# SCH_DHT_projetos_2022-03-18.net
KiCad netlist of a schematic drawn in EasyEDA
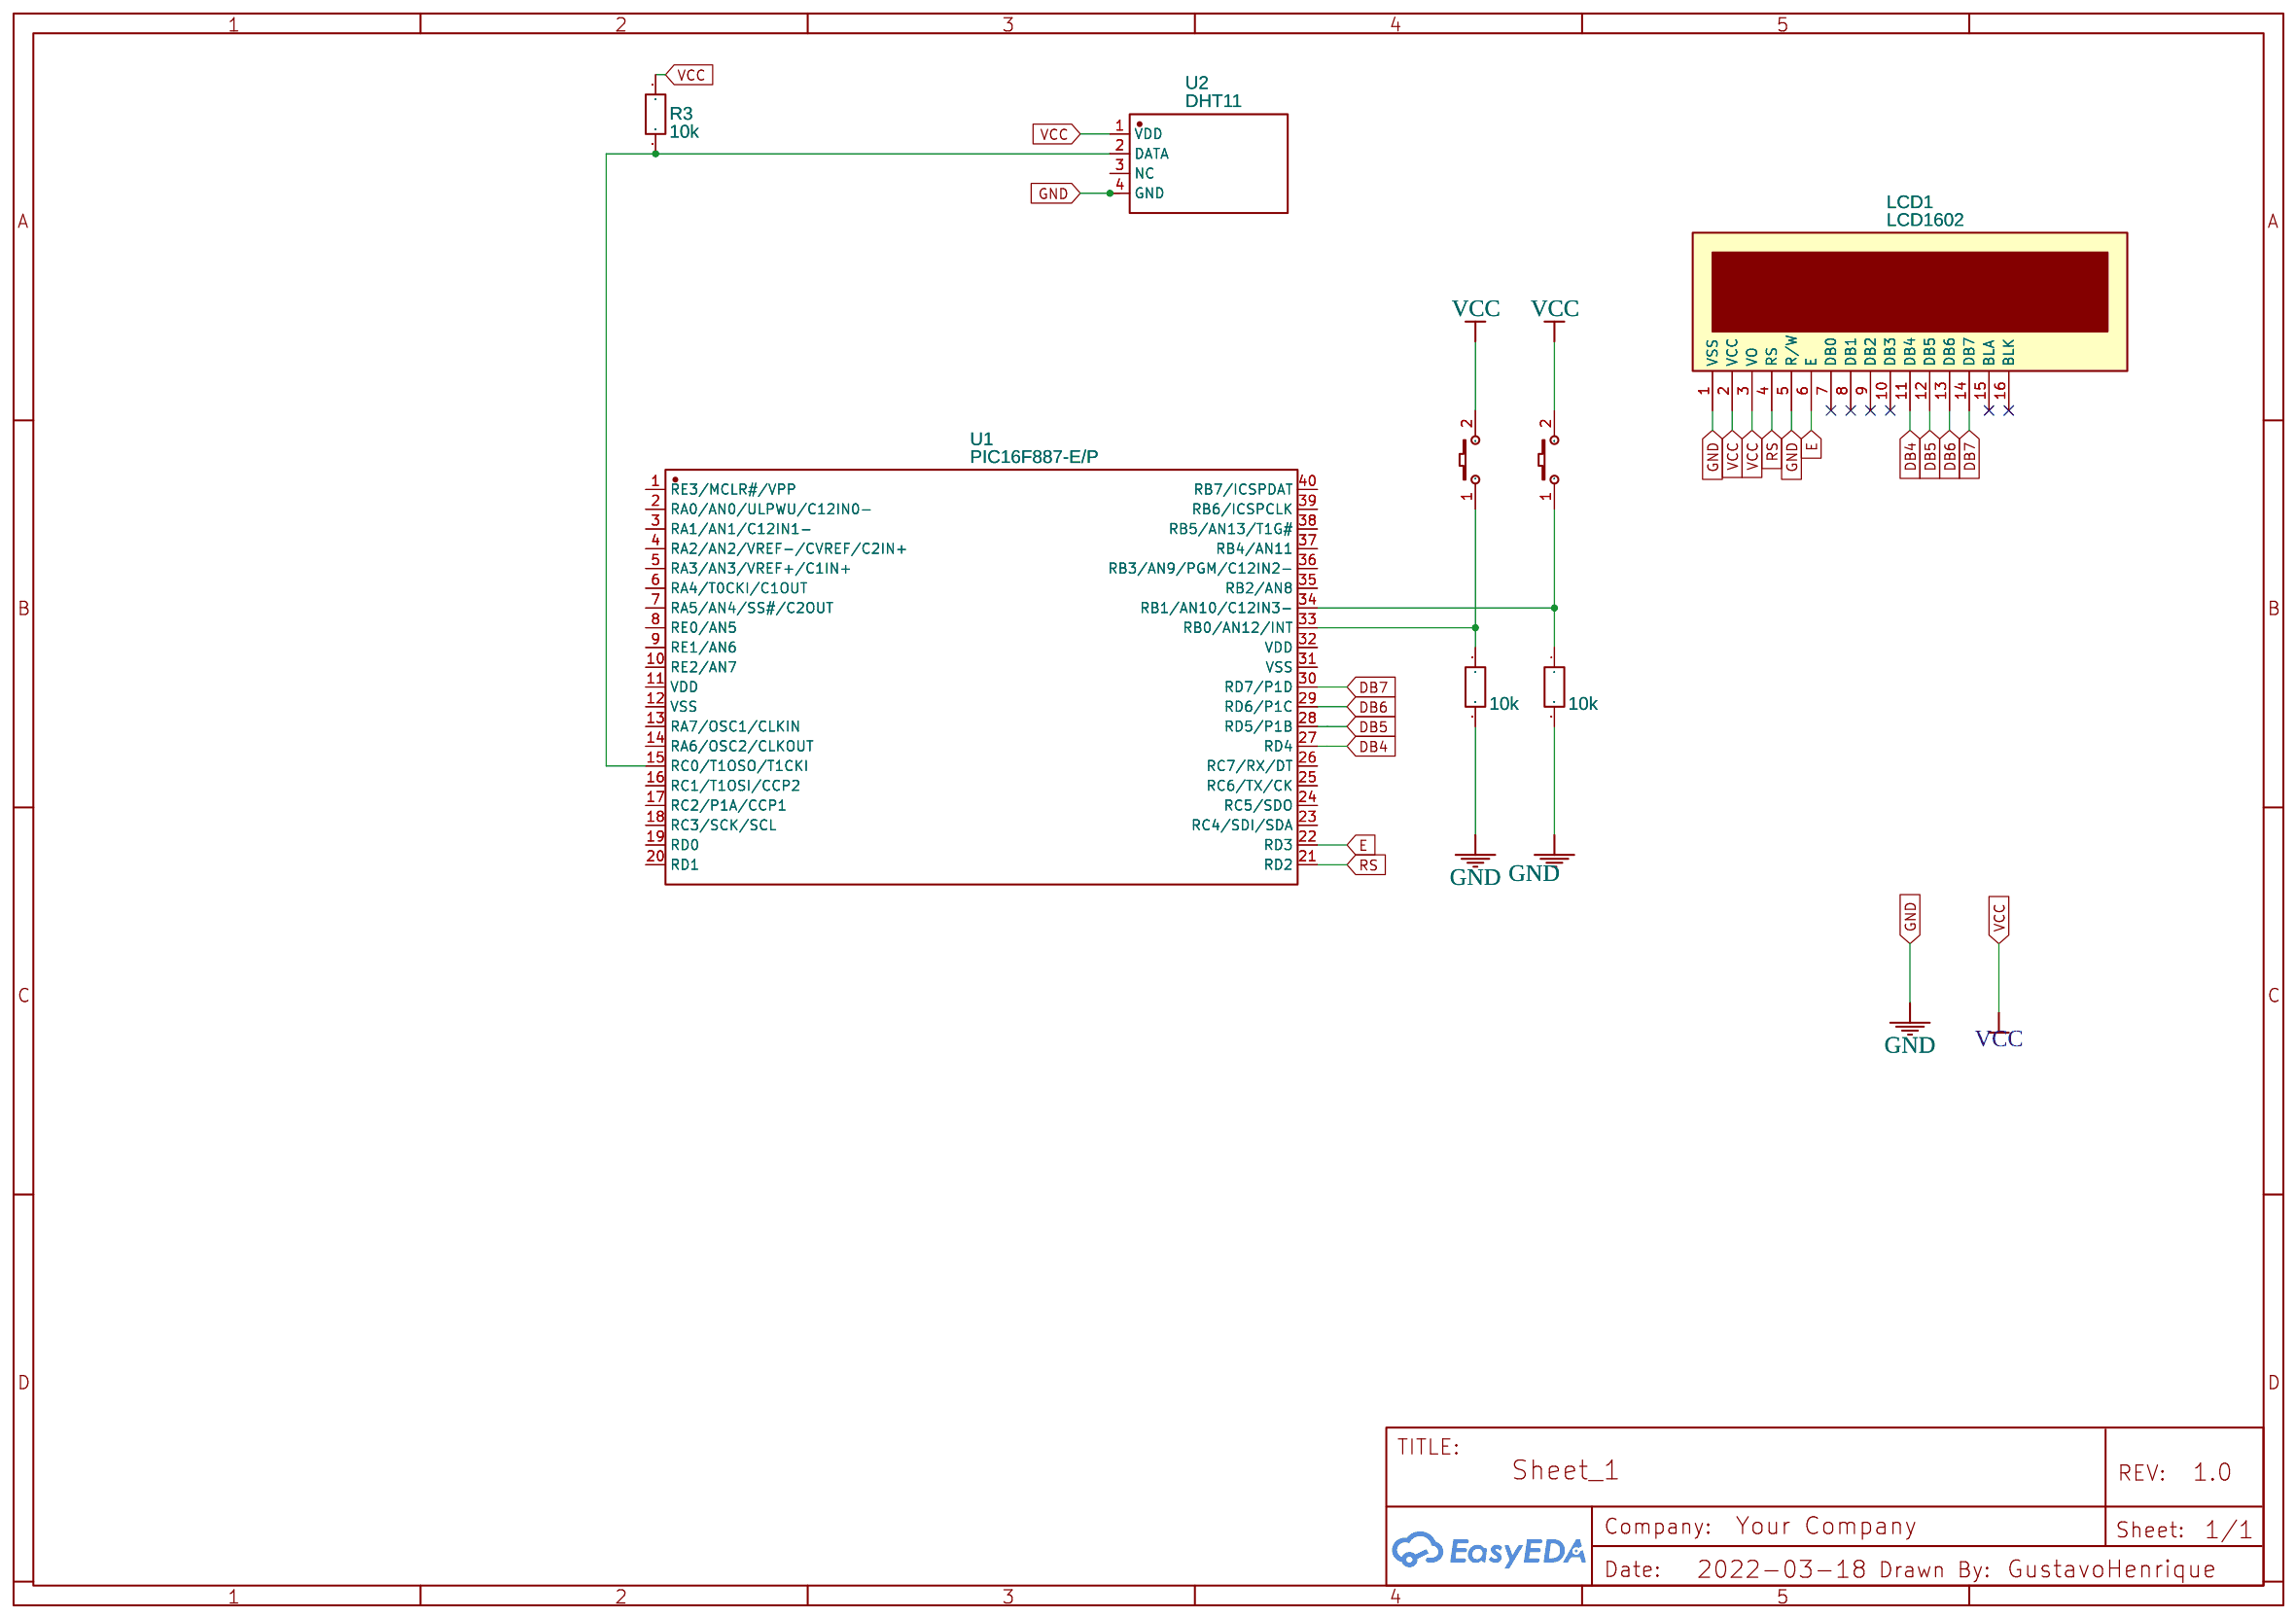
[diagram p0: schematic sheet]

(export (version "E")
  (design (tool "Eeschema 10.0.6"))
  (components
    (comp (ref "KEY1")
      (value "K2-3.6×6.1_SMD")
      (fields
        (field (name "BOM_Manufacturer Part") "K2-1107ST-A4SW-06")
        (field (name "BOM_Supplier Part") "C118141")
      )
      (libsource (lib "") (part "K2-3.6×6.1_SMD"))
    )
    (comp (ref "KEY2")
      (value "K2-3.6×6.1_SMD")
      (fields
        (field (name "BOM_Manufacturer Part") "K2-1107ST-A4SW-06")
        (field (name "BOM_Supplier Part") "C118141")
      )
      (libsource (lib "") (part "K2-3.6×6.1_SMD"))
    )
    (comp (ref "LCD1")
      (value "LCD1602")
      (fields
        (field (name "BOM_Manufacturer Part") "LCM1602K-NSW-BBW")
        (field (name "BOM_Supplier Part") "C83275")
      )
      (libsource (lib "") (part "LCD1602"))
    )
    (comp (ref "R1") (value "10k") (libsource (lib "") (part "R_0603_EU")))
    (comp (ref "R2") (value "10k") (libsource (lib "") (part "R_0603_EU")))
    (comp (ref "R3") (value "10k") (libsource (lib "") (part "R_0603_EU")))
    (comp (ref "U1")
      (value "PIC16F887-E/P")
      (fields (field (name "BOM_Supplier Part") "C647863"))
      (libsource (lib "") (part "PIC16F887-E/P"))
    )
    (comp (ref "U2")
      (value "DHT11")
      (fields (field (name "BOM_Supplier Part") "C117051"))
      (libsource (lib "") (part "DHT11"))
    )
  )
  (nets
    (net (code "1") (name "DB4") (class "Default")
      (node (ref "LCD1") (pin "11") (pinfunction "DB4_11") (pintype "unspecified"))
      (node (ref "U1") (pin "27") (pinfunction "RD4_27") (pintype "unspecified"))
    )
    (net (code "2") (name "DB5") (class "Default")
      (node (ref "LCD1") (pin "12") (pinfunction "DB5_12") (pintype "unspecified"))
      (node (ref "U1") (pin "28") (pinfunction "RD5/P1B_28") (pintype "unspecified"))
    )
    (net (code "3") (name "DB6") (class "Default")
      (node (ref "LCD1") (pin "13") (pinfunction "DB6_13") (pintype "unspecified"))
      (node (ref "U1") (pin "29") (pinfunction "RD6/P1C_29") (pintype "unspecified"))
    )
    (net (code "4") (name "DB7") (class "Default")
      (node (ref "LCD1") (pin "14") (pinfunction "DB7_14") (pintype "unspecified"))
      (node (ref "U1") (pin "30") (pinfunction "RD7/P1D_30") (pintype "unspecified"))
    )
    (net (code "5") (name "E") (class "Default")
      (node (ref "LCD1") (pin "6") (pinfunction "E_6") (pintype "unspecified"))
      (node (ref "U1") (pin "22") (pinfunction "RD3_22") (pintype "unspecified"))
    )
    (net (code "6") (name "GND") (class "Default")
      (node (ref "LCD1") (pin "1") (pinfunction "VSS_1") (pintype "unspecified"))
      (node (ref "LCD1") (pin "5") (pinfunction "R/W_5") (pintype "unspecified"))
      (node (ref "R1") (pin "2") (pinfunction "2_2") (pintype "unspecified"))
      (node (ref "R2") (pin "2") (pinfunction "2_2") (pintype "unspecified"))
      (node (ref "U2") (pin "4") (pinfunction "GND_4") (pintype "unspecified"))
    )
    (net (code "7") (name "Net-(U1-RB0{slash}AN12{slash}INT)") (class "Default")
      (node (ref "KEY1") (pin "1") (pinfunction "1_1") (pintype "unspecified"))
      (node (ref "R1") (pin "1") (pinfunction "1_1") (pintype "unspecified"))
      (node (ref "U1") (pin "33") (pinfunction "RB0/AN12/INT_33") (pintype "unspecified"))
    )
    (net (code "8") (name "Net-(U1-RB1{slash}AN10{slash}C12IN3-)") (class "Default")
      (node (ref "KEY2") (pin "1") (pinfunction "1_1") (pintype "unspecified"))
      (node (ref "R2") (pin "1") (pinfunction "1_1") (pintype "unspecified"))
      (node (ref "U1") (pin "34") (pinfunction "RB1/AN10/C12IN3-_34") (pintype "unspecified"))
    )
    (net (code "9") (name "Net-(U1-RC0{slash}T1OSO{slash}T1CKI)") (class "Default")
      (node (ref "R3") (pin "2") (pinfunction "2_2") (pintype "unspecified"))
      (node (ref "U1") (pin "15") (pinfunction "RC0/T1OSO/T1CKI_15") (pintype "unspecified"))
      (node (ref "U2") (pin "2") (pinfunction "DATA_2") (pintype "unspecified"))
    )
    (net (code "10") (name "RS") (class "Default")
      (node (ref "LCD1") (pin "4") (pinfunction "RS_4") (pintype "unspecified"))
      (node (ref "U1") (pin "21") (pinfunction "RD2_21") (pintype "unspecified"))
    )
    (net (code "11") (name "VCC") (class "Default")
      (node (ref "KEY1") (pin "2") (pinfunction "2_2") (pintype "unspecified"))
      (node (ref "KEY2") (pin "2") (pinfunction "2_2") (pintype "unspecified"))
      (node (ref "LCD1") (pin "2") (pinfunction "VCC_2") (pintype "unspecified"))
      (node (ref "LCD1") (pin "3") (pinfunction "VO_3") (pintype "unspecified"))
      (node (ref "R3") (pin "1") (pinfunction "1_1") (pintype "unspecified"))
      (node (ref "U2") (pin "1") (pinfunction "VDD_1") (pintype "unspecified"))
    )
    (net (code "12") (name "unconnected-(LCD1-BLA-Pad15)") (class "Default")
      (node (ref "LCD1") (pin "15") (pinfunction "BLA_15") (pintype "unspecified+no_connect"))
    )
    (net (code "13") (name "unconnected-(LCD1-BLK-Pad16)") (class "Default")
      (node (ref "LCD1") (pin "16") (pinfunction "BLK_16") (pintype "unspecified+no_connect"))
    )
    (net (code "14") (name "unconnected-(LCD1-DB0-Pad7)") (class "Default")
      (node (ref "LCD1") (pin "7") (pinfunction "DB0_7") (pintype "unspecified+no_connect"))
    )
    (net (code "15") (name "unconnected-(LCD1-DB1-Pad8)") (class "Default")
      (node (ref "LCD1") (pin "8") (pinfunction "DB1_8") (pintype "unspecified+no_connect"))
    )
    (net (code "16") (name "unconnected-(LCD1-DB2-Pad9)") (class "Default")
      (node (ref "LCD1") (pin "9") (pinfunction "DB2_9") (pintype "unspecified+no_connect"))
    )
    (net (code "17") (name "unconnected-(LCD1-DB3-Pad10)") (class "Default")
      (node (ref "LCD1") (pin "10") (pinfunction "DB3_10") (pintype "unspecified+no_connect"))
    )
    (net (code "18") (name "unconnected-(U1-RA0{slash}AN0{slash}ULPWU{slash}C12IN0--Pad2)") (class "Default")
      (node (ref "U1") (pin "2") (pinfunction "RA0/AN0/ULPWU/C12IN0-_2") (pintype "unspecified"))
    )
    (net (code "19") (name "unconnected-(U1-RA1{slash}AN1{slash}C12IN1--Pad3)") (class "Default")
      (node (ref "U1") (pin "3") (pinfunction "RA1/AN1/C12IN1-_3") (pintype "unspecified"))
    )
    (net (code "20") (name "unconnected-(U1-RA2{slash}AN2{slash}VREF-{slash}CVREF{slash}C2IN+-Pad4)") (class "Default")
      (node (ref "U1") (pin "4") (pinfunction "RA2/AN2/VREF-/CVREF/C2IN+_4") (pintype "unspecified"))
    )
    (net (code "21") (name "unconnected-(U1-RA3{slash}AN3{slash}VREF+{slash}C1IN+-Pad5)") (class "Default")
      (node (ref "U1") (pin "5") (pinfunction "RA3/AN3/VREF+/C1IN+_5") (pintype "unspecified"))
    )
    (net (code "22") (name "unconnected-(U1-RA4{slash}T0CKI{slash}C1OUT-Pad6)") (class "Default")
      (node (ref "U1") (pin "6") (pinfunction "RA4/T0CKI/C1OUT_6") (pintype "unspecified"))
    )
    (net (code "23") (name "unconnected-(U1-RA5{slash}AN4{slash}SS#{slash}C2OUT-Pad7)") (class "Default")
      (node (ref "U1") (pin "7") (pinfunction "RA5/AN4/SS#/C2OUT_7") (pintype "unspecified"))
    )
    (net (code "24") (name "unconnected-(U1-RA6{slash}OSC2{slash}CLKOUT-Pad14)") (class "Default")
      (node (ref "U1") (pin "14") (pinfunction "RA6/OSC2/CLKOUT_14") (pintype "unspecified"))
    )
    (net (code "25") (name "unconnected-(U1-RA7{slash}OSC1{slash}CLKIN-Pad13)") (class "Default")
      (node (ref "U1") (pin "13") (pinfunction "RA7/OSC1/CLKIN_13") (pintype "unspecified"))
    )
    (net (code "26") (name "unconnected-(U1-RB2{slash}AN8-Pad35)") (class "Default")
      (node (ref "U1") (pin "35") (pinfunction "RB2/AN8_35") (pintype "unspecified"))
    )
    (net (code "27") (name "unconnected-(U1-RB3{slash}AN9{slash}PGM{slash}C12IN2--Pad36)") (class "Default")
      (node (ref "U1") (pin "36") (pinfunction "RB3/AN9/PGM/C12IN2-_36") (pintype "unspecified"))
    )
    (net (code "28") (name "unconnected-(U1-RB4{slash}AN11-Pad37)") (class "Default")
      (node (ref "U1") (pin "37") (pinfunction "RB4/AN11_37") (pintype "unspecified"))
    )
    (net (code "29") (name "unconnected-(U1-RB5{slash}AN13{slash}T1G#-Pad38)") (class "Default")
      (node (ref "U1") (pin "38") (pinfunction "RB5/AN13/T1G#_38") (pintype "unspecified"))
    )
    (net (code "30") (name "unconnected-(U1-RB6{slash}ICSPCLK-Pad39)") (class "Default")
      (node (ref "U1") (pin "39") (pinfunction "RB6/ICSPCLK_39") (pintype "unspecified"))
    )
    (net (code "31") (name "unconnected-(U1-RB7{slash}ICSPDAT-Pad40)") (class "Default")
      (node (ref "U1") (pin "40") (pinfunction "RB7/ICSPDAT_40") (pintype "unspecified"))
    )
    (net (code "32") (name "unconnected-(U1-RC1{slash}T1OSI{slash}CCP2-Pad16)") (class "Default")
      (node (ref "U1") (pin "16") (pinfunction "RC1/T1OSI/CCP2_16") (pintype "unspecified"))
    )
    (net (code "33") (name "unconnected-(U1-RC2{slash}P1A{slash}CCP1-Pad17)") (class "Default")
      (node (ref "U1") (pin "17") (pinfunction "RC2/P1A/CCP1_17") (pintype "unspecified"))
    )
    (net (code "34") (name "unconnected-(U1-RC3{slash}SCK{slash}SCL-Pad18)") (class "Default")
      (node (ref "U1") (pin "18") (pinfunction "RC3/SCK/SCL_18") (pintype "unspecified"))
    )
    (net (code "35") (name "unconnected-(U1-RC4{slash}SDI{slash}SDA-Pad23)") (class "Default")
      (node (ref "U1") (pin "23") (pinfunction "RC4/SDI/SDA_23") (pintype "unspecified"))
    )
    (net (code "36") (name "unconnected-(U1-RC5{slash}SDO-Pad24)") (class "Default")
      (node (ref "U1") (pin "24") (pinfunction "RC5/SDO_24") (pintype "unspecified"))
    )
    (net (code "37") (name "unconnected-(U1-RC6{slash}TX{slash}CK-Pad25)") (class "Default")
      (node (ref "U1") (pin "25") (pinfunction "RC6/TX/CK_25") (pintype "unspecified"))
    )
    (net (code "38") (name "unconnected-(U1-RC7{slash}RX{slash}DT-Pad26)") (class "Default")
      (node (ref "U1") (pin "26") (pinfunction "RC7/RX/DT_26") (pintype "unspecified"))
    )
    (net (code "39") (name "unconnected-(U1-RD0-Pad19)") (class "Default")
      (node (ref "U1") (pin "19") (pinfunction "RD0_19") (pintype "unspecified"))
    )
    (net (code "40") (name "unconnected-(U1-RD1-Pad20)") (class "Default")
      (node (ref "U1") (pin "20") (pinfunction "RD1_20") (pintype "unspecified"))
    )
    (net (code "41") (name "unconnected-(U1-RE0{slash}AN5-Pad8)") (class "Default")
      (node (ref "U1") (pin "8") (pinfunction "RE0/AN5_8") (pintype "unspecified"))
    )
    (net (code "42") (name "unconnected-(U1-RE1{slash}AN6-Pad9)") (class "Default")
      (node (ref "U1") (pin "9") (pinfunction "RE1/AN6_9") (pintype "unspecified"))
    )
    (net (code "43") (name "unconnected-(U1-RE2{slash}AN7-Pad10)") (class "Default")
      (node (ref "U1") (pin "10") (pinfunction "RE2/AN7_10") (pintype "unspecified"))
    )
    (net (code "44") (name "unconnected-(U1-RE3{slash}MCLR#{slash}VPP-Pad1)") (class "Default")
      (node (ref "U1") (pin "1") (pinfunction "RE3/MCLR#/VPP_1") (pintype "unspecified"))
    )
    (net (code "45") (name "unconnected-(U1-VDD-Pad11)") (class "Default")
      (node (ref "U1") (pin "11") (pinfunction "VDD_11") (pintype "unspecified"))
    )
    (net (code "46") (name "unconnected-(U1-VDD-Pad32)") (class "Default")
      (node (ref "U1") (pin "32") (pinfunction "VDD_32") (pintype "unspecified"))
    )
    (net (code "47") (name "unconnected-(U1-VSS-Pad12)") (class "Default")
      (node (ref "U1") (pin "12") (pinfunction "VSS_12") (pintype "unspecified"))
    )
    (net (code "48") (name "unconnected-(U1-VSS-Pad31)") (class "Default")
      (node (ref "U1") (pin "31") (pinfunction "VSS_31") (pintype "unspecified"))
    )
    (net (code "49") (name "unconnected-(U2-NC-Pad3)") (class "Default")
      (node (ref "U2") (pin "3") (pinfunction "NC_3") (pintype "unspecified"))
    )
  )
)
